# 4-UniverseOutV2.net
KiCad netlist of a schematic drawn in EAGLE
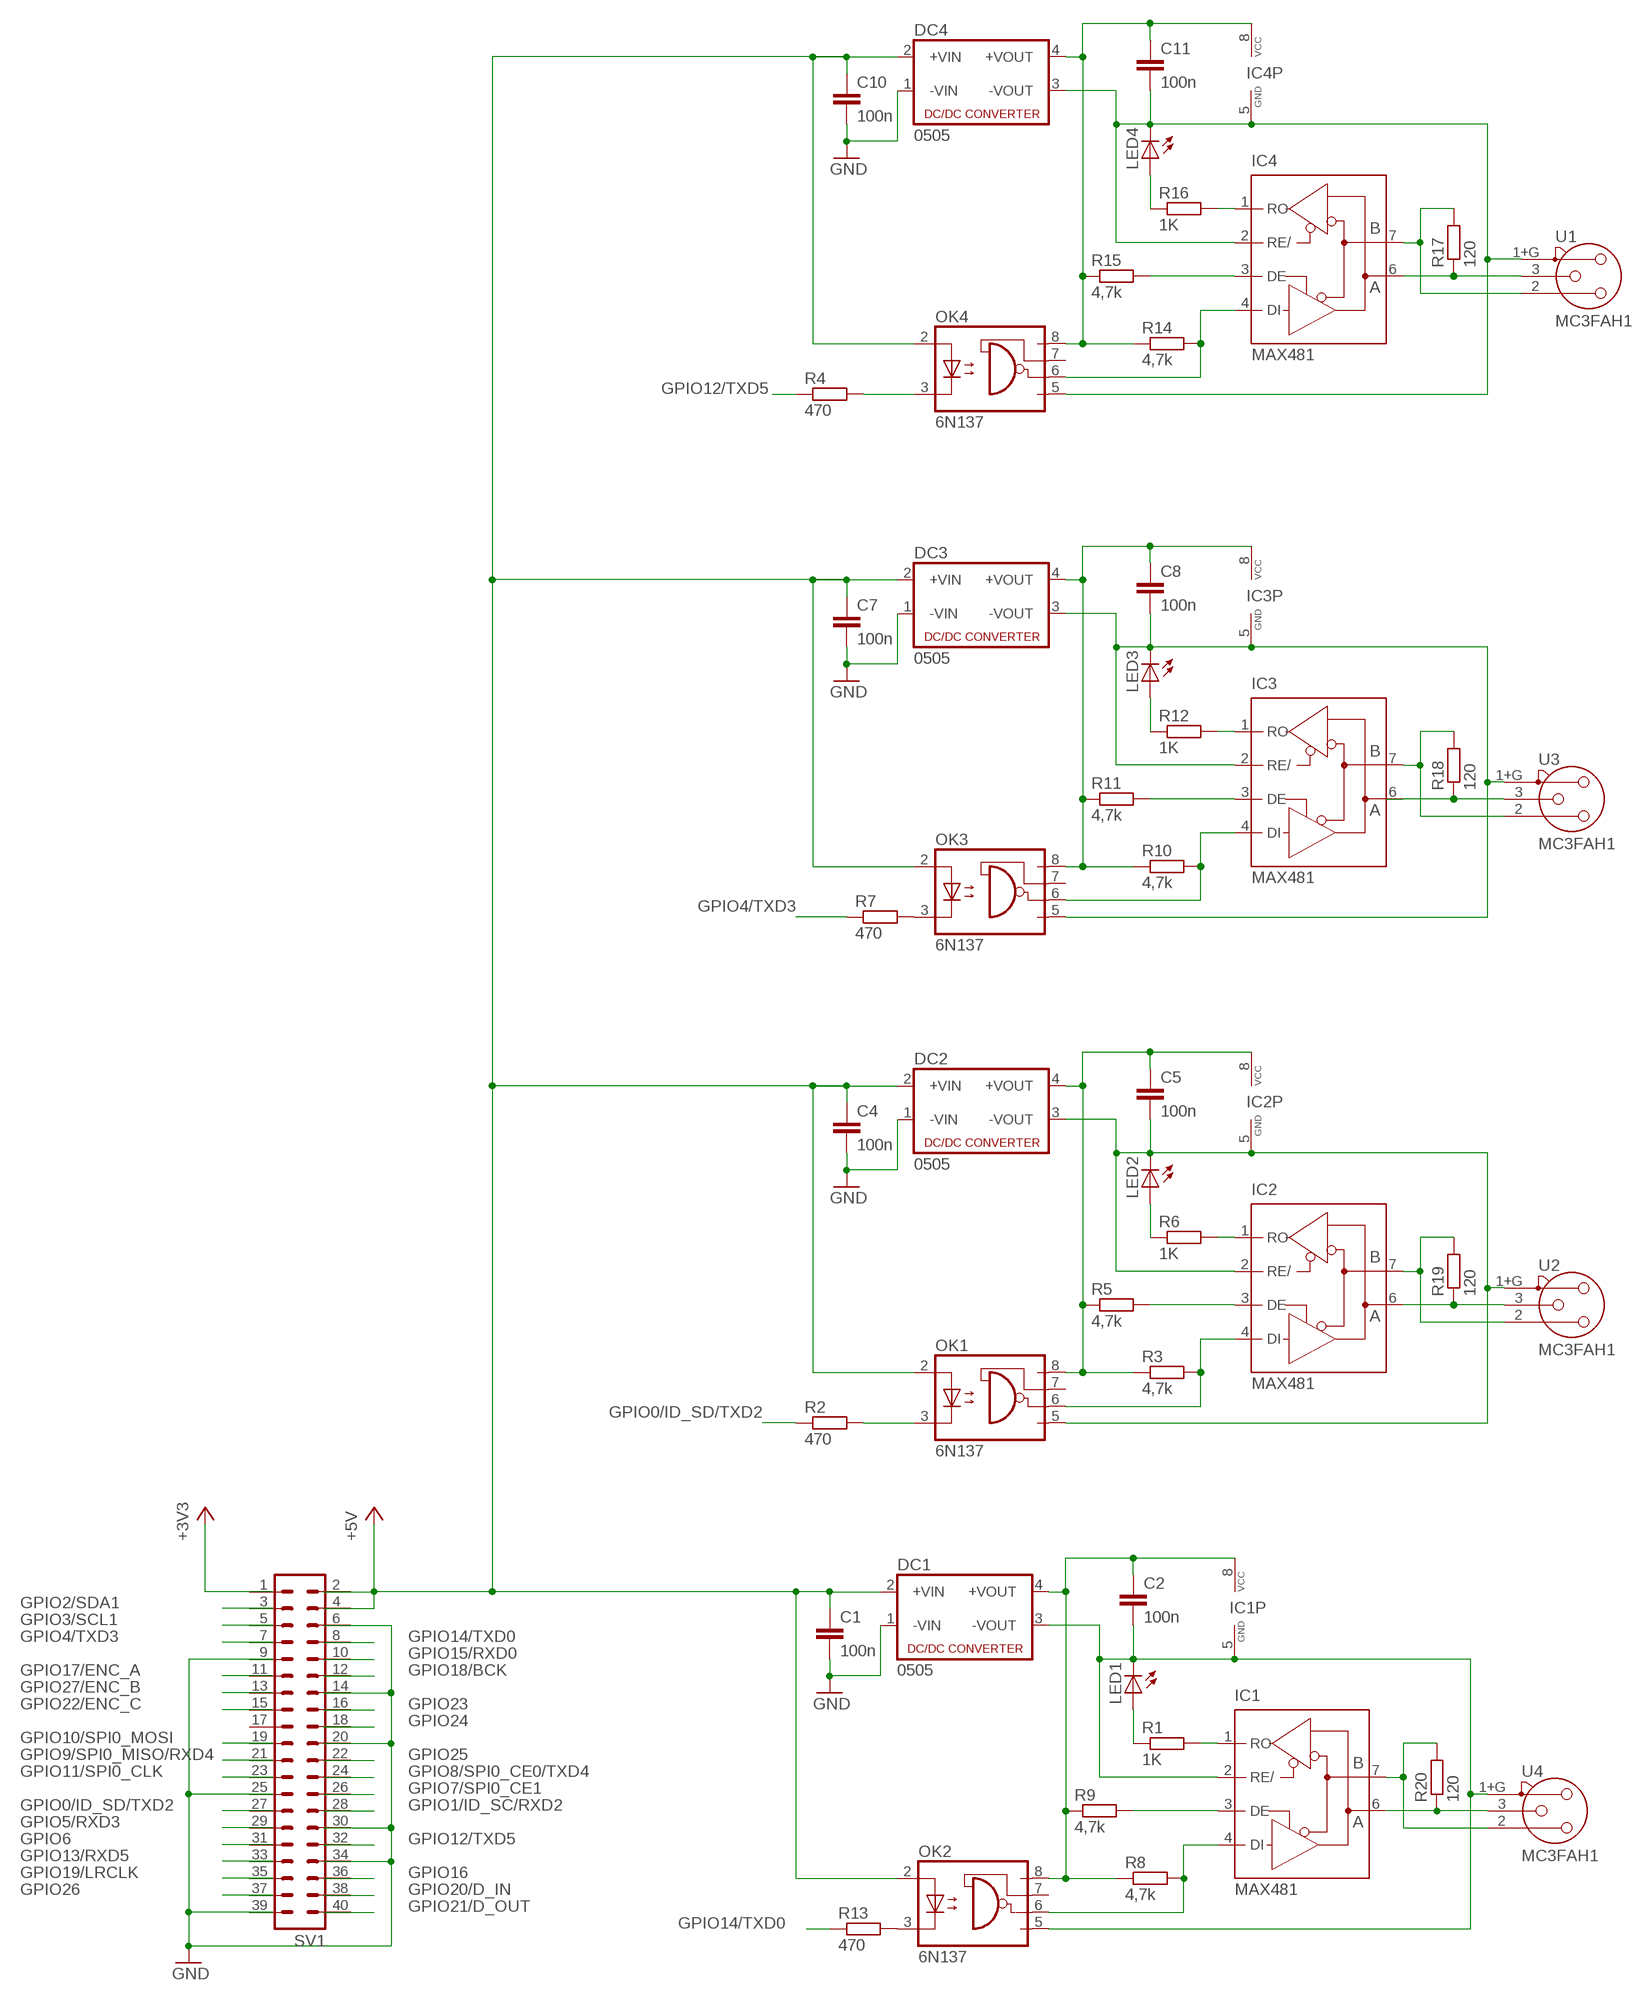
[diagram p0: schematic, sheet 1]

(export (version "E")
  (design (tool "Eeschema 10.0.6"))
  (components
    (comp (ref "C1")
      (value "100n")
      (footprint "eagle-import:C5B3")
      (libsource (lib "eagle-import") (part "C5/3"))
    )
    (comp (ref "C2")
      (value "100n")
      (footprint "eagle-import:C7.5B3")
      (libsource (lib "eagle-import") (part "C7.5/3"))
    )
    (comp (ref "C4")
      (value "100n")
      (footprint "eagle-import:C5B3")
      (libsource (lib "eagle-import") (part "C5/3"))
    )
    (comp (ref "C5")
      (value "100n")
      (footprint "eagle-import:C7.5B3")
      (libsource (lib "eagle-import") (part "C7.5/3"))
    )
    (comp (ref "C7")
      (value "100n")
      (footprint "eagle-import:C5B3")
      (libsource (lib "eagle-import") (part "C5/3"))
    )
    (comp (ref "C8")
      (value "100n")
      (footprint "eagle-import:C7.5B3")
      (libsource (lib "eagle-import") (part "C7.5/3"))
    )
    (comp (ref "C10")
      (value "100n")
      (footprint "eagle-import:C5B3")
      (libsource (lib "eagle-import") (part "C5/3"))
    )
    (comp (ref "C11")
      (value "100n")
      (footprint "eagle-import:C7.5B3")
      (libsource (lib "eagle-import") (part "C7.5/3"))
    )
    (comp (ref "DC1")
      (value "0505")
      (footprint "eagle-import:NME")
      (fields (field (name "MF") "C & D TECHNOLOGIES, INC") (field (name "MPN") "NME1205D"))
      (libsource (lib "eagle-import") (part "NME"))
    )
    (comp (ref "DC2")
      (value "0505")
      (footprint "eagle-import:NME")
      (fields (field (name "MF") "C & D TECHNOLOGIES, INC") (field (name "MPN") "NME1205D"))
      (libsource (lib "eagle-import") (part "NME"))
    )
    (comp (ref "DC3")
      (value "0505")
      (footprint "eagle-import:NME")
      (fields (field (name "MF") "C & D TECHNOLOGIES, INC") (field (name "MPN") "NME1205D"))
      (libsource (lib "eagle-import") (part "NME"))
    )
    (comp (ref "DC4")
      (value "0505")
      (footprint "eagle-import:NME")
      (fields (field (name "MF") "C & D TECHNOLOGIES, INC") (field (name "MPN") "NME1205D"))
      (libsource (lib "eagle-import") (part "NME"))
    )
    (comp (ref "IC1")
      (value "MAX481")
      (footprint "eagle-import:DIL08")
      (fields (field (name "MPN") "MAX481CPA+"))
      (libsource (lib "eagle-import") (part "MAX481CPA"))
    )
    (comp (ref "IC2")
      (value "MAX481")
      (footprint "eagle-import:DIL08")
      (fields (field (name "MPN") "MAX481CPA+"))
      (libsource (lib "eagle-import") (part "MAX481CPA"))
    )
    (comp (ref "IC3")
      (value "MAX481")
      (footprint "eagle-import:DIL08")
      (fields (field (name "MPN") "MAX481CPA+"))
      (libsource (lib "eagle-import") (part "MAX481CPA"))
    )
    (comp (ref "IC4")
      (value "MAX481")
      (footprint "eagle-import:DIL08")
      (fields (field (name "MPN") "MAX481CPA+"))
      (libsource (lib "eagle-import") (part "MAX481CPA"))
    )
    (comp (ref "LED1")
      (value "LED3MM")
      (footprint "eagle-import:LED3MM")
      (libsource (lib "eagle-import") (part "LED3MM"))
    )
    (comp (ref "LED2")
      (value "LED3MM")
      (footprint "eagle-import:LED3MM")
      (libsource (lib "eagle-import") (part "LED3MM"))
    )
    (comp (ref "LED3")
      (value "LED3MM")
      (footprint "eagle-import:LED3MM")
      (libsource (lib "eagle-import") (part "LED3MM"))
    )
    (comp (ref "LED4")
      (value "LED3MM")
      (footprint "eagle-import:LED3MM")
      (libsource (lib "eagle-import") (part "LED3MM"))
    )
    (comp (ref "OK1")
      (value "6N137")
      (footprint "eagle-import:DIL08")
      (libsource (lib "eagle-import") (part "6N137"))
    )
    (comp (ref "OK2")
      (value "6N137")
      (footprint "eagle-import:DIL08")
      (libsource (lib "eagle-import") (part "6N137"))
    )
    (comp (ref "OK3")
      (value "6N137")
      (footprint "eagle-import:DIL08")
      (libsource (lib "eagle-import") (part "6N137"))
    )
    (comp (ref "OK4")
      (value "6N137")
      (footprint "eagle-import:DIL08")
      (libsource (lib "eagle-import") (part "6N137"))
    )
    (comp (ref "R1")
      (value "1K")
      (footprint "eagle-import:0204_7")
      (libsource (lib "eagle-import") (part "R-EU_0204/7"))
    )
    (comp (ref "R2")
      (value "470")
      (footprint "eagle-import:0204_7")
      (libsource (lib "eagle-import") (part "R-EU_0204/7"))
    )
    (comp (ref "R3")
      (value "4,7k")
      (footprint "eagle-import:0204_7")
      (libsource (lib "eagle-import") (part "R-EU_0204/7"))
    )
    (comp (ref "R4")
      (value "470")
      (footprint "eagle-import:0204_7")
      (libsource (lib "eagle-import") (part "R-EU_0204/7"))
    )
    (comp (ref "R5")
      (value "4,7k")
      (footprint "eagle-import:0204_7")
      (libsource (lib "eagle-import") (part "R-EU_0204/7"))
    )
    (comp (ref "R6")
      (value "1K")
      (footprint "eagle-import:0204_7")
      (libsource (lib "eagle-import") (part "R-EU_0204/7"))
    )
    (comp (ref "R7")
      (value "470")
      (footprint "eagle-import:0204_7")
      (libsource (lib "eagle-import") (part "R-EU_0204/7"))
    )
    (comp (ref "R8")
      (value "4,7k")
      (footprint "eagle-import:0204_7")
      (libsource (lib "eagle-import") (part "R-EU_0204/7"))
    )
    (comp (ref "R9")
      (value "4,7k")
      (footprint "eagle-import:0204_7")
      (libsource (lib "eagle-import") (part "R-EU_0204/7"))
    )
    (comp (ref "R10")
      (value "4,7k")
      (footprint "eagle-import:0204_7")
      (libsource (lib "eagle-import") (part "R-EU_0204/7"))
    )
    (comp (ref "R11")
      (value "4,7k")
      (footprint "eagle-import:0204_7")
      (libsource (lib "eagle-import") (part "R-EU_0204/7"))
    )
    (comp (ref "R12")
      (value "1K")
      (footprint "eagle-import:0204_7")
      (libsource (lib "eagle-import") (part "R-EU_0204/7"))
    )
    (comp (ref "R13")
      (value "470")
      (footprint "eagle-import:0204_7")
      (libsource (lib "eagle-import") (part "R-EU_0204/7"))
    )
    (comp (ref "R14")
      (value "4,7k")
      (footprint "eagle-import:0204_7")
      (libsource (lib "eagle-import") (part "R-EU_0204/7"))
    )
    (comp (ref "R15")
      (value "4,7k")
      (footprint "eagle-import:0204_7")
      (libsource (lib "eagle-import") (part "R-EU_0204/7"))
    )
    (comp (ref "R16")
      (value "1K")
      (footprint "eagle-import:0204_7")
      (libsource (lib "eagle-import") (part "R-EU_0204/7"))
    )
    (comp (ref "R17")
      (value "120")
      (footprint "eagle-import:0207_2V")
      (libsource (lib "eagle-import") (part "R-EU_0207/2V"))
    )
    (comp (ref "R18")
      (value "120")
      (footprint "eagle-import:0207_2V")
      (libsource (lib "eagle-import") (part "R-EU_0207/2V"))
    )
    (comp (ref "R19")
      (value "120")
      (footprint "eagle-import:0207_2V")
      (libsource (lib "eagle-import") (part "R-EU_0207/2V"))
    )
    (comp (ref "R20")
      (value "120")
      (footprint "eagle-import:0207_2V")
      (libsource (lib "eagle-import") (part "R-EU_0207/2V"))
    )
    (comp (ref "SV1")
      (value "ML40")
      (footprint "eagle-import:ML40")
      (libsource (lib "eagle-import") (part "ML40"))
    )
    (comp (ref "U1")
      (value "MC3FAH1")
      (footprint "eagle-import:NC3FAH1")
      (libsource (lib "eagle-import") (part "MC3?FAH1"))
    )
    (comp (ref "U2")
      (value "MC3FAH1")
      (footprint "eagle-import:NC3FAH1")
      (libsource (lib "eagle-import") (part "MC3?FAH1"))
    )
    (comp (ref "U3")
      (value "MC3FAH1")
      (footprint "eagle-import:NC3FAH1")
      (libsource (lib "eagle-import") (part "MC3?FAH1"))
    )
    (comp (ref "U4")
      (value "MC3FAH1")
      (footprint "eagle-import:NC3FAH1")
      (libsource (lib "eagle-import") (part "MC3?FAH1"))
    )
  )
  (nets
    (net (code "1") (name "+3V3") (class "Default")
      (node (ref "SV1") (pin "1") (pinfunction "1_1") (pintype "passive"))
    )
    (net (code "2") (name "+5V") (class "Default")
      (node (ref "C1") (pin "1") (pinfunction "1_1") (pintype "passive"))
      (node (ref "C10") (pin "1") (pinfunction "1_1") (pintype "passive"))
      (node (ref "C4") (pin "1") (pinfunction "1_1") (pintype "passive"))
      (node (ref "C7") (pin "1") (pinfunction "1_1") (pintype "passive"))
      (node (ref "DC1") (pin "2") (pinfunction "+VIN_2") (pintype "passive"))
      (node (ref "DC2") (pin "2") (pinfunction "+VIN_2") (pintype "passive"))
      (node (ref "DC3") (pin "2") (pinfunction "+VIN_2") (pintype "passive"))
      (node (ref "DC4") (pin "2") (pinfunction "+VIN_2") (pintype "passive"))
      (node (ref "OK1") (pin "2") (pinfunction "A_2") (pintype "passive"))
      (node (ref "OK2") (pin "2") (pinfunction "A_2") (pintype "passive"))
      (node (ref "OK3") (pin "2") (pinfunction "A_2") (pintype "passive"))
      (node (ref "OK4") (pin "2") (pinfunction "A_2") (pintype "passive"))
      (node (ref "SV1") (pin "2") (pinfunction "2_2") (pintype "passive"))
      (node (ref "SV1") (pin "4") (pinfunction "4_4") (pintype "passive"))
    )
    (net (code "3") (name "/GPIO0{slash}ID_SD{slash}TXD2") (class "Default")
      (node (ref "R2") (pin "1") (pinfunction "1_1") (pintype "passive"))
      (node (ref "SV1") (pin "27") (pinfunction "27_27") (pintype "passive"))
    )
    (net (code "4") (name "/GPIO1{slash}ID_SC{slash}RXD2") (class "Default")
      (node (ref "SV1") (pin "28") (pinfunction "28_28") (pintype "passive"))
    )
    (net (code "5") (name "/GPIO2{slash}SDA1") (class "Default")
      (node (ref "SV1") (pin "3") (pinfunction "3_3") (pintype "passive"))
    )
    (net (code "6") (name "/GPIO3{slash}SCL1") (class "Default")
      (node (ref "SV1") (pin "5") (pinfunction "5_5") (pintype "passive"))
    )
    (net (code "7") (name "/GPIO4{slash}TXD3") (class "Default")
      (node (ref "R7") (pin "1") (pinfunction "1_1") (pintype "passive"))
      (node (ref "SV1") (pin "7") (pinfunction "7_7") (pintype "passive"))
    )
    (net (code "8") (name "/GPIO5{slash}RXD3") (class "Default")
      (node (ref "SV1") (pin "29") (pinfunction "29_29") (pintype "passive"))
    )
    (net (code "9") (name "/GPIO6") (class "Default")
      (node (ref "SV1") (pin "31") (pinfunction "31_31") (pintype "passive"))
    )
    (net (code "10") (name "/GPIO7{slash}SPI0_CE1") (class "Default")
      (node (ref "SV1") (pin "26") (pinfunction "26_26") (pintype "passive"))
    )
    (net (code "11") (name "/GPIO8{slash}SPI0_CE0{slash}TXD4") (class "Default")
      (node (ref "SV1") (pin "24") (pinfunction "24_24") (pintype "passive"))
    )
    (net (code "12") (name "/GPIO9{slash}SPI0_MISO{slash}RXD4") (class "Default")
      (node (ref "SV1") (pin "21") (pinfunction "21_21") (pintype "passive"))
    )
    (net (code "13") (name "/GPIO10{slash}SPI0_MOSI") (class "Default")
      (node (ref "SV1") (pin "19") (pinfunction "19_19") (pintype "passive"))
    )
    (net (code "14") (name "/GPIO11{slash}SPI0_CLK") (class "Default")
      (node (ref "SV1") (pin "23") (pinfunction "23_23") (pintype "passive"))
    )
    (net (code "15") (name "/GPIO12{slash}TXD5") (class "Default")
      (node (ref "R4") (pin "1") (pinfunction "1_1") (pintype "passive"))
      (node (ref "SV1") (pin "32") (pinfunction "32_32") (pintype "passive"))
    )
    (net (code "16") (name "/GPIO13{slash}RXD5") (class "Default")
      (node (ref "SV1") (pin "33") (pinfunction "33_33") (pintype "passive"))
    )
    (net (code "17") (name "/GPIO14{slash}TXD0") (class "Default")
      (node (ref "R13") (pin "1") (pinfunction "1_1") (pintype "passive"))
      (node (ref "SV1") (pin "8") (pinfunction "8_8") (pintype "passive"))
    )
    (net (code "18") (name "/GPIO15{slash}RXD0") (class "Default")
      (node (ref "SV1") (pin "10") (pinfunction "10_10") (pintype "passive"))
    )
    (net (code "19") (name "/GPIO16") (class "Default")
      (node (ref "SV1") (pin "36") (pinfunction "36_36") (pintype "passive"))
    )
    (net (code "20") (name "/GPIO17{slash}ENC_A") (class "Default")
      (node (ref "SV1") (pin "11") (pinfunction "11_11") (pintype "passive"))
    )
    (net (code "21") (name "/GPIO18{slash}BCK") (class "Default")
      (node (ref "SV1") (pin "12") (pinfunction "12_12") (pintype "passive"))
    )
    (net (code "22") (name "/GPIO19{slash}LRCLK") (class "Default")
      (node (ref "SV1") (pin "35") (pinfunction "35_35") (pintype "passive"))
    )
    (net (code "23") (name "/GPIO20{slash}D_IN") (class "Default")
      (node (ref "SV1") (pin "38") (pinfunction "38_38") (pintype "passive"))
    )
    (net (code "24") (name "/GPIO21{slash}D_OUT") (class "Default")
      (node (ref "SV1") (pin "40") (pinfunction "40_40") (pintype "passive"))
    )
    (net (code "25") (name "/GPIO22{slash}ENC_C") (class "Default")
      (node (ref "SV1") (pin "15") (pinfunction "15_15") (pintype "passive"))
    )
    (net (code "26") (name "/GPIO23") (class "Default")
      (node (ref "SV1") (pin "16") (pinfunction "16_16") (pintype "passive"))
    )
    (net (code "27") (name "/GPIO24") (class "Default")
      (node (ref "SV1") (pin "18") (pinfunction "18_18") (pintype "passive"))
    )
    (net (code "28") (name "/GPIO25") (class "Default")
      (node (ref "SV1") (pin "22") (pinfunction "22_22") (pintype "passive"))
    )
    (net (code "29") (name "/GPIO26") (class "Default")
      (node (ref "SV1") (pin "37") (pinfunction "37_37") (pintype "passive"))
    )
    (net (code "30") (name "/GPIO27{slash}ENC_B") (class "Default")
      (node (ref "SV1") (pin "13") (pinfunction "13_13") (pintype "passive"))
    )
    (net (code "31") (name "GND") (class "Default")
      (node (ref "C1") (pin "2") (pinfunction "2_2") (pintype "passive"))
      (node (ref "C10") (pin "2") (pinfunction "2_2") (pintype "passive"))
      (node (ref "C4") (pin "2") (pinfunction "2_2") (pintype "passive"))
      (node (ref "C7") (pin "2") (pinfunction "2_2") (pintype "passive"))
      (node (ref "DC1") (pin "1") (pinfunction "-VIN_1") (pintype "passive"))
      (node (ref "DC2") (pin "1") (pinfunction "-VIN_1") (pintype "passive"))
      (node (ref "DC3") (pin "1") (pinfunction "-VIN_1") (pintype "passive"))
      (node (ref "DC4") (pin "1") (pinfunction "-VIN_1") (pintype "passive"))
      (node (ref "SV1") (pin "14") (pinfunction "14_14") (pintype "passive"))
      (node (ref "SV1") (pin "20") (pinfunction "20_20") (pintype "passive"))
      (node (ref "SV1") (pin "25") (pinfunction "25_25") (pintype "passive"))
      (node (ref "SV1") (pin "30") (pinfunction "30_30") (pintype "passive"))
      (node (ref "SV1") (pin "34") (pinfunction "34_34") (pintype "passive"))
      (node (ref "SV1") (pin "39") (pinfunction "39_39") (pintype "passive"))
      (node (ref "SV1") (pin "6") (pinfunction "6_6") (pintype "passive"))
      (node (ref "SV1") (pin "9") (pinfunction "9_9") (pintype "passive"))
    )
    (net (code "32") (name "Net-(DC1-+VOUT)") (class "Default")
      (node (ref "C2") (pin "1") (pinfunction "1_1") (pintype "passive"))
      (node (ref "DC1") (pin "4") (pinfunction "+VOUT_4") (pintype "passive"))
      (node (ref "IC1") (pin "8") (pinfunction "VCC_8") (pintype "power_in"))
      (node (ref "OK2") (pin "8") (pinfunction "VCC_8") (pintype "passive"))
      (node (ref "R8") (pin "1") (pinfunction "1_1") (pintype "passive"))
      (node (ref "R9") (pin "1") (pinfunction "1_1") (pintype "passive"))
    )
    (net (code "33") (name "Net-(DC1--VOUT)") (class "Default")
      (node (ref "C2") (pin "2") (pinfunction "2_2") (pintype "passive"))
      (node (ref "DC1") (pin "3") (pinfunction "-VOUT_3") (pintype "passive"))
      (node (ref "IC1") (pin "2") (pinfunction "RE/_2") (pintype "input"))
      (node (ref "IC1") (pin "5") (pinfunction "GND_5") (pintype "power_in"))
      (node (ref "LED1") (pin "K") (pinfunction "C_K") (pintype "passive"))
      (node (ref "OK2") (pin "5") (pinfunction "GND_5") (pintype "passive"))
      (node (ref "U4") (pin "1+G") (pinfunction "1_1+G") (pintype "passive"))
    )
    (net (code "34") (name "Net-(DC2-+VOUT)") (class "Default")
      (node (ref "C5") (pin "1") (pinfunction "1_1") (pintype "passive"))
      (node (ref "DC2") (pin "4") (pinfunction "+VOUT_4") (pintype "passive"))
      (node (ref "IC2") (pin "8") (pinfunction "VCC_8") (pintype "power_in"))
      (node (ref "OK1") (pin "8") (pinfunction "VCC_8") (pintype "passive"))
      (node (ref "R3") (pin "1") (pinfunction "1_1") (pintype "passive"))
      (node (ref "R5") (pin "1") (pinfunction "1_1") (pintype "passive"))
    )
    (net (code "35") (name "Net-(DC2--VOUT)") (class "Default")
      (node (ref "C5") (pin "2") (pinfunction "2_2") (pintype "passive"))
      (node (ref "DC2") (pin "3") (pinfunction "-VOUT_3") (pintype "passive"))
      (node (ref "IC2") (pin "2") (pinfunction "RE/_2") (pintype "input"))
      (node (ref "IC2") (pin "5") (pinfunction "GND_5") (pintype "power_in"))
      (node (ref "LED2") (pin "K") (pinfunction "C_K") (pintype "passive"))
      (node (ref "OK1") (pin "5") (pinfunction "GND_5") (pintype "passive"))
      (node (ref "U2") (pin "1+G") (pinfunction "1_1+G") (pintype "passive"))
    )
    (net (code "36") (name "Net-(DC3-+VOUT)") (class "Default")
      (node (ref "C8") (pin "1") (pinfunction "1_1") (pintype "passive"))
      (node (ref "DC3") (pin "4") (pinfunction "+VOUT_4") (pintype "passive"))
      (node (ref "IC3") (pin "8") (pinfunction "VCC_8") (pintype "power_in"))
      (node (ref "OK3") (pin "8") (pinfunction "VCC_8") (pintype "passive"))
      (node (ref "R10") (pin "1") (pinfunction "1_1") (pintype "passive"))
      (node (ref "R11") (pin "1") (pinfunction "1_1") (pintype "passive"))
    )
    (net (code "37") (name "Net-(DC3--VOUT)") (class "Default")
      (node (ref "C8") (pin "2") (pinfunction "2_2") (pintype "passive"))
      (node (ref "DC3") (pin "3") (pinfunction "-VOUT_3") (pintype "passive"))
      (node (ref "IC3") (pin "2") (pinfunction "RE/_2") (pintype "input"))
      (node (ref "IC3") (pin "5") (pinfunction "GND_5") (pintype "power_in"))
      (node (ref "LED3") (pin "K") (pinfunction "C_K") (pintype "passive"))
      (node (ref "OK3") (pin "5") (pinfunction "GND_5") (pintype "passive"))
      (node (ref "U3") (pin "1+G") (pinfunction "1_1+G") (pintype "passive"))
    )
    (net (code "38") (name "Net-(DC4-+VOUT)") (class "Default")
      (node (ref "C11") (pin "1") (pinfunction "1_1") (pintype "passive"))
      (node (ref "DC4") (pin "4") (pinfunction "+VOUT_4") (pintype "passive"))
      (node (ref "IC4") (pin "8") (pinfunction "VCC_8") (pintype "power_in"))
      (node (ref "OK4") (pin "8") (pinfunction "VCC_8") (pintype "passive"))
      (node (ref "R14") (pin "1") (pinfunction "1_1") (pintype "passive"))
      (node (ref "R15") (pin "1") (pinfunction "1_1") (pintype "passive"))
    )
    (net (code "39") (name "Net-(DC4--VOUT)") (class "Default")
      (node (ref "C11") (pin "2") (pinfunction "2_2") (pintype "passive"))
      (node (ref "DC4") (pin "3") (pinfunction "-VOUT_3") (pintype "passive"))
      (node (ref "IC4") (pin "2") (pinfunction "RE/_2") (pintype "input"))
      (node (ref "IC4") (pin "5") (pinfunction "GND_5") (pintype "power_in"))
      (node (ref "LED4") (pin "K") (pinfunction "C_K") (pintype "passive"))
      (node (ref "OK4") (pin "5") (pinfunction "GND_5") (pintype "passive"))
      (node (ref "U1") (pin "1+G") (pinfunction "1_1+G") (pintype "passive"))
    )
    (net (code "40") (name "Net-(IC1A-A)") (class "Default")
      (node (ref "IC1") (pin "6") (pinfunction "A_6") (pintype "passive"))
      (node (ref "R20") (pin "1") (pinfunction "1_1") (pintype "passive"))
      (node (ref "U4") (pin "3") (pinfunction "3_3") (pintype "passive"))
    )
    (net (code "41") (name "Net-(IC1A-B)") (class "Default")
      (node (ref "IC1") (pin "7") (pinfunction "B_7") (pintype "passive"))
      (node (ref "R20") (pin "2") (pinfunction "2_2") (pintype "passive"))
      (node (ref "U4") (pin "2") (pinfunction "2_2") (pintype "passive"))
    )
    (net (code "42") (name "Net-(IC1A-DE)") (class "Default")
      (node (ref "IC1") (pin "3") (pinfunction "DE_3") (pintype "input"))
      (node (ref "R9") (pin "2") (pinfunction "2_2") (pintype "passive"))
    )
    (net (code "43") (name "Net-(IC1A-DI)") (class "Default")
      (node (ref "IC1") (pin "4") (pinfunction "DI_4") (pintype "input"))
      (node (ref "OK2") (pin "6") (pinfunction "VO_6") (pintype "passive"))
      (node (ref "R8") (pin "2") (pinfunction "2_2") (pintype "passive"))
    )
    (net (code "44") (name "Net-(IC1A-RO)") (class "Default")
      (node (ref "IC1") (pin "1") (pinfunction "RO_1") (pintype "output"))
      (node (ref "R1") (pin "2") (pinfunction "2_2") (pintype "passive"))
    )
    (net (code "45") (name "Net-(IC2A-A)") (class "Default")
      (node (ref "IC2") (pin "6") (pinfunction "A_6") (pintype "passive"))
      (node (ref "R19") (pin "1") (pinfunction "1_1") (pintype "passive"))
      (node (ref "U2") (pin "3") (pinfunction "3_3") (pintype "passive"))
    )
    (net (code "46") (name "Net-(IC2A-B)") (class "Default")
      (node (ref "IC2") (pin "7") (pinfunction "B_7") (pintype "passive"))
      (node (ref "R19") (pin "2") (pinfunction "2_2") (pintype "passive"))
      (node (ref "U2") (pin "2") (pinfunction "2_2") (pintype "passive"))
    )
    (net (code "47") (name "Net-(IC2A-DE)") (class "Default")
      (node (ref "IC2") (pin "3") (pinfunction "DE_3") (pintype "input"))
      (node (ref "R5") (pin "2") (pinfunction "2_2") (pintype "passive"))
    )
    (net (code "48") (name "Net-(IC2A-DI)") (class "Default")
      (node (ref "IC2") (pin "4") (pinfunction "DI_4") (pintype "input"))
      (node (ref "OK1") (pin "6") (pinfunction "VO_6") (pintype "passive"))
      (node (ref "R3") (pin "2") (pinfunction "2_2") (pintype "passive"))
    )
    (net (code "49") (name "Net-(IC2A-RO)") (class "Default")
      (node (ref "IC2") (pin "1") (pinfunction "RO_1") (pintype "output"))
      (node (ref "R6") (pin "2") (pinfunction "2_2") (pintype "passive"))
    )
    (net (code "50") (name "Net-(IC3A-A)") (class "Default")
      (node (ref "IC3") (pin "6") (pinfunction "A_6") (pintype "passive"))
      (node (ref "R18") (pin "1") (pinfunction "1_1") (pintype "passive"))
      (node (ref "U3") (pin "3") (pinfunction "3_3") (pintype "passive"))
    )
    (net (code "51") (name "Net-(IC3A-B)") (class "Default")
      (node (ref "IC3") (pin "7") (pinfunction "B_7") (pintype "passive"))
      (node (ref "R18") (pin "2") (pinfunction "2_2") (pintype "passive"))
      (node (ref "U3") (pin "2") (pinfunction "2_2") (pintype "passive"))
    )
    (net (code "52") (name "Net-(IC3A-DE)") (class "Default")
      (node (ref "IC3") (pin "3") (pinfunction "DE_3") (pintype "input"))
      (node (ref "R11") (pin "2") (pinfunction "2_2") (pintype "passive"))
    )
    (net (code "53") (name "Net-(IC3A-DI)") (class "Default")
      (node (ref "IC3") (pin "4") (pinfunction "DI_4") (pintype "input"))
      (node (ref "OK3") (pin "6") (pinfunction "VO_6") (pintype "passive"))
      (node (ref "R10") (pin "2") (pinfunction "2_2") (pintype "passive"))
    )
    (net (code "54") (name "Net-(IC3A-RO)") (class "Default")
      (node (ref "IC3") (pin "1") (pinfunction "RO_1") (pintype "output"))
      (node (ref "R12") (pin "2") (pinfunction "2_2") (pintype "passive"))
    )
    (net (code "55") (name "Net-(IC4A-A)") (class "Default")
      (node (ref "IC4") (pin "6") (pinfunction "A_6") (pintype "passive"))
      (node (ref "R17") (pin "1") (pinfunction "1_1") (pintype "passive"))
      (node (ref "U1") (pin "3") (pinfunction "3_3") (pintype "passive"))
    )
    (net (code "56") (name "Net-(IC4A-B)") (class "Default")
      (node (ref "IC4") (pin "7") (pinfunction "B_7") (pintype "passive"))
      (node (ref "R17") (pin "2") (pinfunction "2_2") (pintype "passive"))
      (node (ref "U1") (pin "2") (pinfunction "2_2") (pintype "passive"))
    )
    (net (code "57") (name "Net-(IC4A-DE)") (class "Default")
      (node (ref "IC4") (pin "3") (pinfunction "DE_3") (pintype "input"))
      (node (ref "R15") (pin "2") (pinfunction "2_2") (pintype "passive"))
    )
    (net (code "58") (name "Net-(IC4A-DI)") (class "Default")
      (node (ref "IC4") (pin "4") (pinfunction "DI_4") (pintype "input"))
      (node (ref "OK4") (pin "6") (pinfunction "VO_6") (pintype "passive"))
      (node (ref "R14") (pin "2") (pinfunction "2_2") (pintype "passive"))
    )
    (net (code "59") (name "Net-(IC4A-RO)") (class "Default")
      (node (ref "IC4") (pin "1") (pinfunction "RO_1") (pintype "output"))
      (node (ref "R16") (pin "2") (pinfunction "2_2") (pintype "passive"))
    )
    (net (code "60") (name "Net-(LED1-PadA)") (class "Default")
      (node (ref "LED1") (pin "A") (pinfunction "A_A") (pintype "passive"))
      (node (ref "R1") (pin "1") (pinfunction "1_1") (pintype "passive"))
    )
    (net (code "61") (name "Net-(LED2-PadA)") (class "Default")
      (node (ref "LED2") (pin "A") (pinfunction "A_A") (pintype "passive"))
      (node (ref "R6") (pin "1") (pinfunction "1_1") (pintype "passive"))
    )
    (net (code "62") (name "Net-(LED3-PadA)") (class "Default")
      (node (ref "LED3") (pin "A") (pinfunction "A_A") (pintype "passive"))
      (node (ref "R12") (pin "1") (pinfunction "1_1") (pintype "passive"))
    )
    (net (code "63") (name "Net-(LED4-PadA)") (class "Default")
      (node (ref "LED4") (pin "A") (pinfunction "A_A") (pintype "passive"))
      (node (ref "R16") (pin "1") (pinfunction "1_1") (pintype "passive"))
    )
    (net (code "64") (name "Net-(OK1-C)") (class "Default")
      (node (ref "OK1") (pin "3") (pinfunction "C_3") (pintype "passive"))
      (node (ref "R2") (pin "2") (pinfunction "2_2") (pintype "passive"))
    )
    (net (code "65") (name "Net-(OK2-C)") (class "Default")
      (node (ref "OK2") (pin "3") (pinfunction "C_3") (pintype "passive"))
      (node (ref "R13") (pin "2") (pinfunction "2_2") (pintype "passive"))
    )
    (net (code "66") (name "Net-(OK3-C)") (class "Default")
      (node (ref "OK3") (pin "3") (pinfunction "C_3") (pintype "passive"))
      (node (ref "R7") (pin "2") (pinfunction "2_2") (pintype "passive"))
    )
    (net (code "67") (name "Net-(OK4-C)") (class "Default")
      (node (ref "OK4") (pin "3") (pinfunction "C_3") (pintype "passive"))
      (node (ref "R4") (pin "2") (pinfunction "2_2") (pintype "passive"))
    )
    (net (code "68") (name "unconnected-(OK1-VE-Pad7)") (class "Default")
      (node (ref "OK1") (pin "7") (pinfunction "VE_7") (pintype "passive"))
    )
    (net (code "69") (name "unconnected-(OK2-VE-Pad7)") (class "Default")
      (node (ref "OK2") (pin "7") (pinfunction "VE_7") (pintype "passive"))
    )
    (net (code "70") (name "unconnected-(OK3-VE-Pad7)") (class "Default")
      (node (ref "OK3") (pin "7") (pinfunction "VE_7") (pintype "passive"))
    )
    (net (code "71") (name "unconnected-(OK4-VE-Pad7)") (class "Default")
      (node (ref "OK4") (pin "7") (pinfunction "VE_7") (pintype "passive"))
    )
    (net (code "72") (name "unconnected-(SV1-Pad17)") (class "Default")
      (node (ref "SV1") (pin "17") (pinfunction "17_17") (pintype "passive"))
    )
  )
)
